# SCH_PCB-Hacker-Card_2024-02-11.net
KiCad netlist of a schematic drawn in EasyEDA
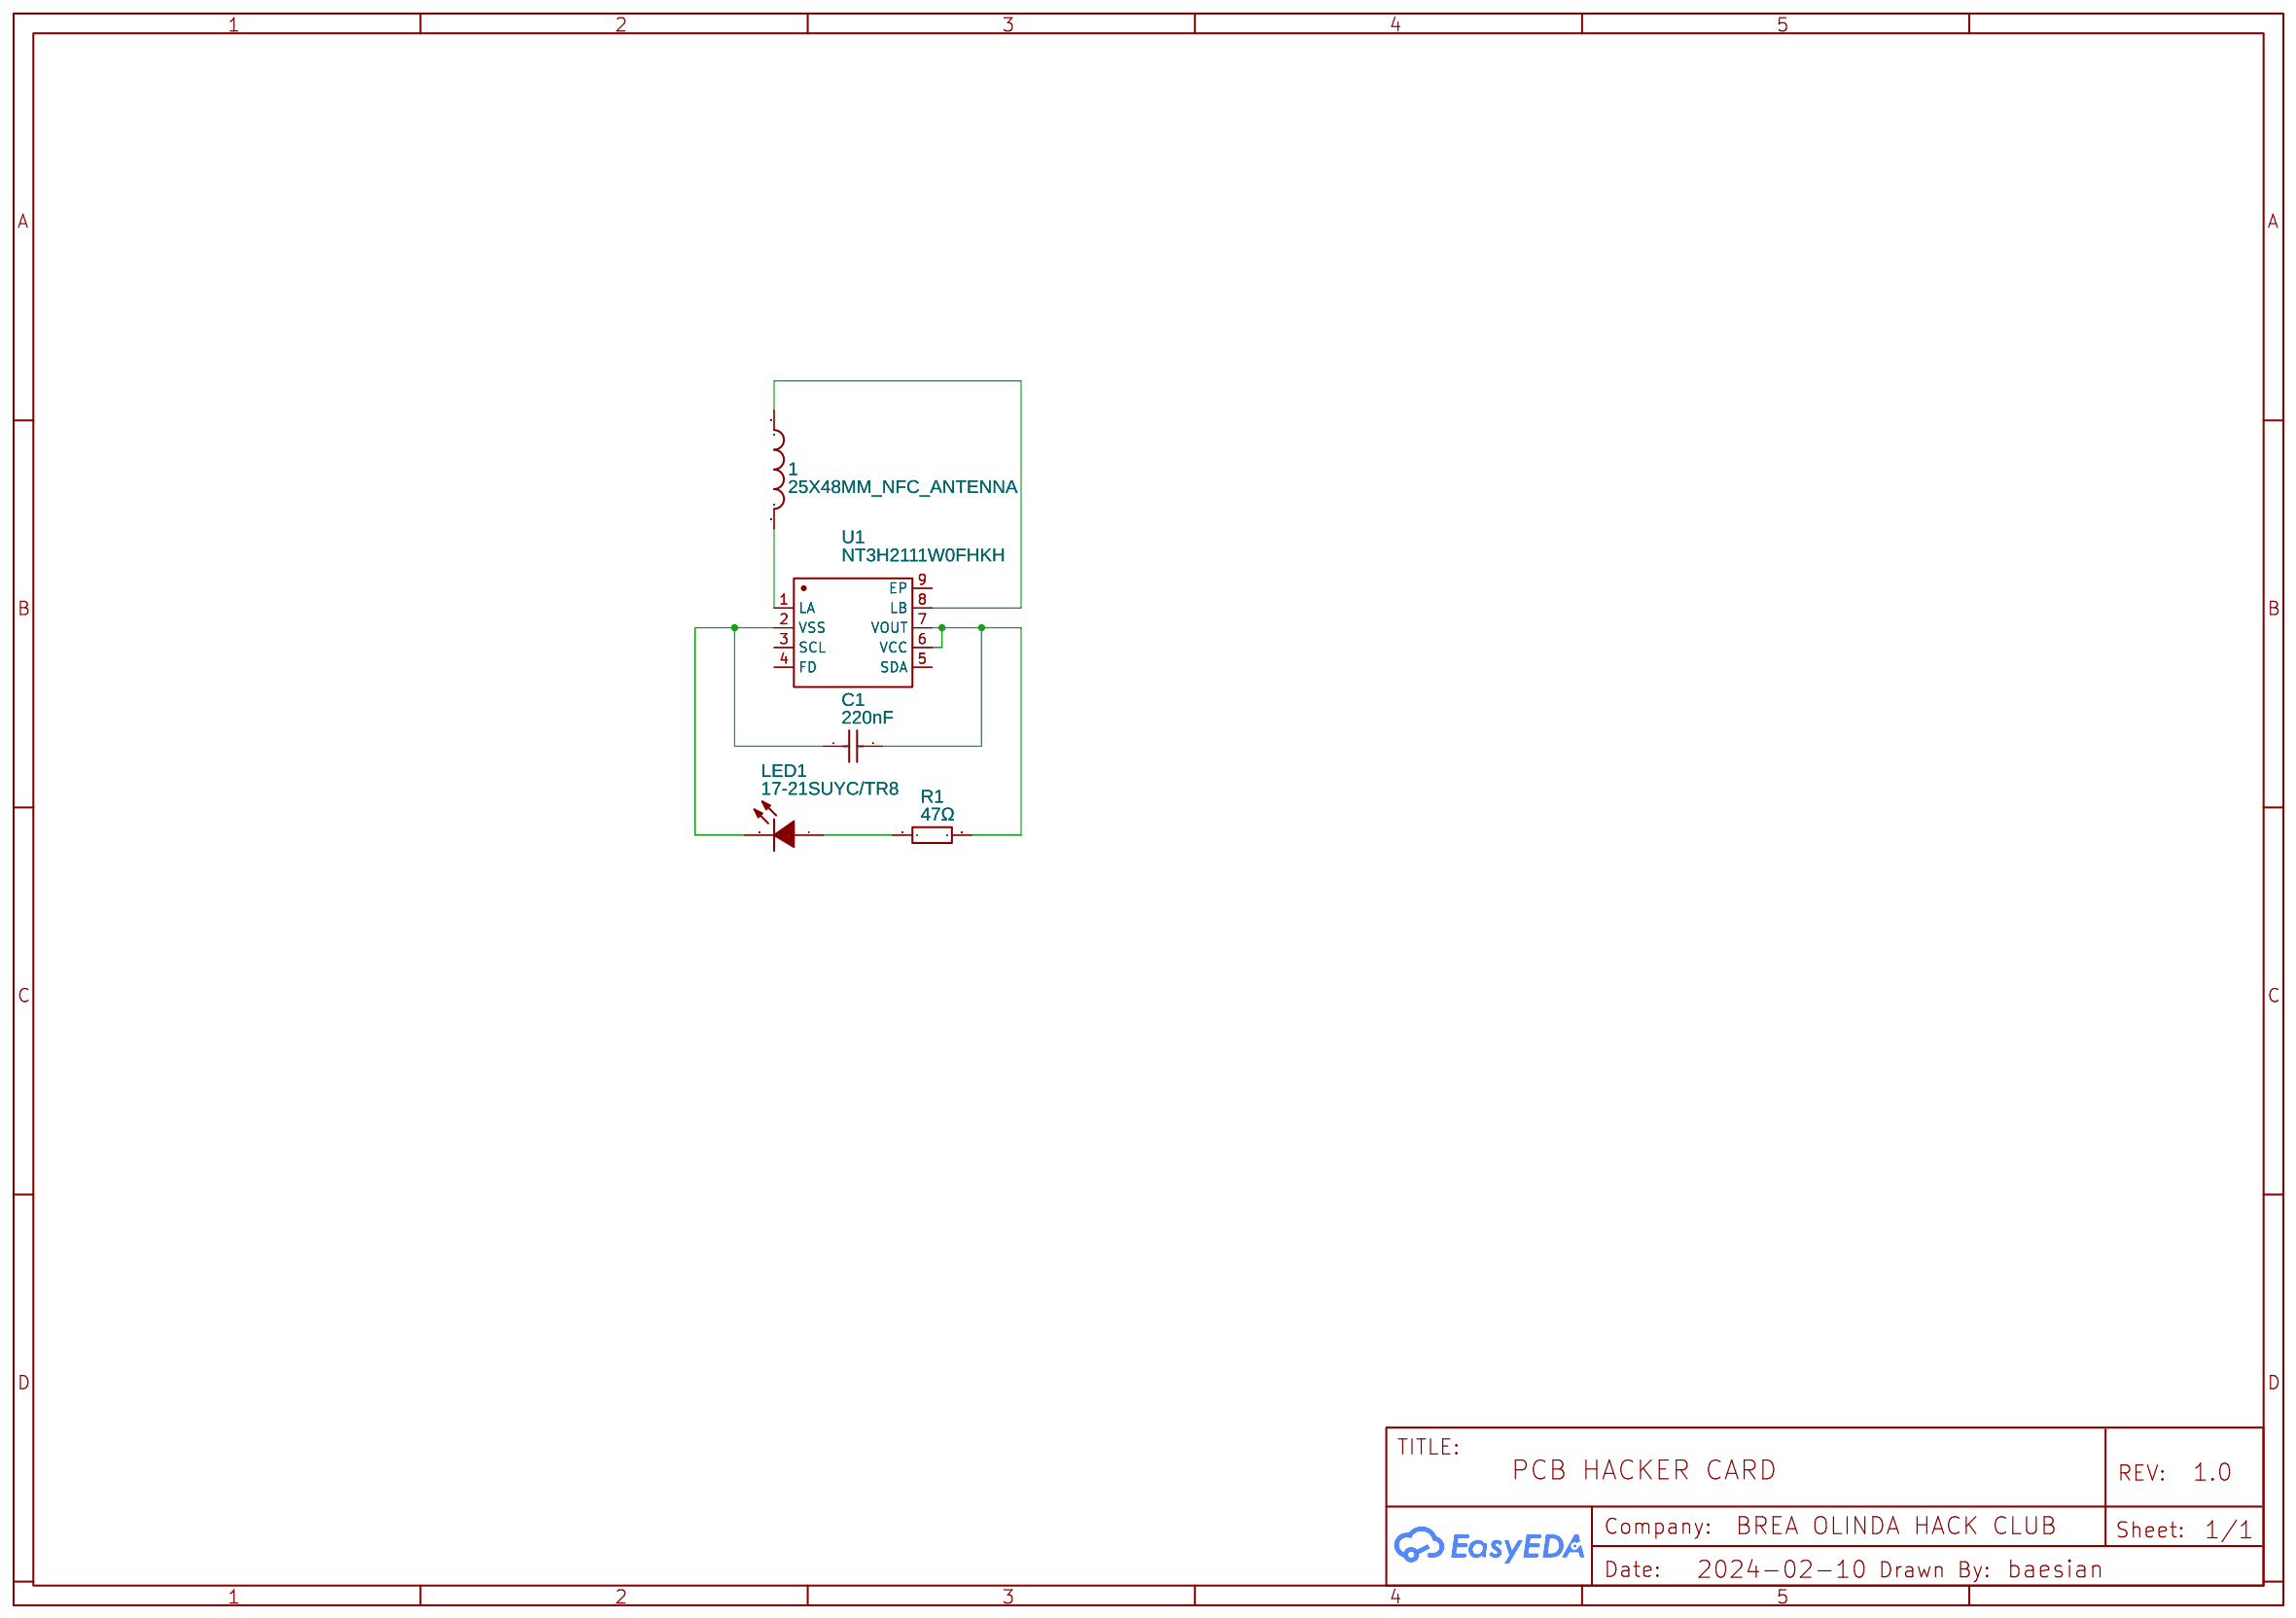
[diagram p0: schematic sheet]

(export (version "E")
  (design (tool "Eeschema 10.0.6"))
  (components
    (comp (ref "1") (value "25X48MM_NFC_ANTENNA") (libsource (lib "") (part "25X48MM_NFC_ANTENNA")))
    (comp (ref "C1")
      (value "220nF")
      (fields
        (field (name "Manufacturer Part") "CL10B224KA8NNNC")
        (field (name "Manufacturer") "SAMSUNG(三星)")
      )
      (libsource (lib "") (part "CL10B224KA8NNNC"))
    )
    (comp (ref "LED1")
      (value "17-21SUYC/TR8")
      (fields (field (name "Manufacturer Part") "KT-0805黄灯") (field (name "Manufacturer") "KENTO"))
      (libsource (lib "") (part "17-21SUYC/TR8"))
    )
    (comp (ref "R1")
      (value "47Ω")
      (fields
        (field (name "Manufacturer Part") "0603WAF470JT5E")
        (field (name "Manufacturer") "UNI-ROYAL(厚声)")
      )
      (libsource (lib "") (part "0603WAF470JT5E"))
    )
    (comp (ref "U1")
      (value "NT3H2111W0FHKH")
      (fields (field (name "Manufacturer") "NXP(恩智浦)"))
      (libsource (lib "") (part "NT3H2111W0FHKH"))
    )
  )
  (nets
    (net (code "1") (name "Net-(LED1-+)") (class "Default")
      (node (ref "LED1") (pin "1") (pinfunction "+_1") (pintype "unspecified"))
      (node (ref "R1") (pin "1") (pinfunction "1_1") (pintype "input"))
    )
    (net (code "2") (name "Net-(LED1--)") (class "Default")
      (node (ref "C1") (pin "1") (pinfunction "1_1") (pintype "input"))
      (node (ref "LED1") (pin "2") (pinfunction "-_2") (pintype "unspecified"))
      (node (ref "U1") (pin "2") (pinfunction "VSS_2") (pintype "unspecified"))
    )
    (net (code "3") (name "Net-(U1-LA)") (class "Default")
      (node (ref "1") (pin "P$2") (pinfunction "P$2_P$2") (pintype "bidirectional"))
      (node (ref "U1") (pin "1") (pinfunction "LA_1") (pintype "unspecified"))
    )
    (net (code "4") (name "Net-(U1-LB)") (class "Default")
      (node (ref "1") (pin "P$1") (pinfunction "P$1_P$1") (pintype "bidirectional"))
      (node (ref "U1") (pin "8") (pinfunction "LB_8") (pintype "unspecified"))
    )
    (net (code "5") (name "Net-(U1-VCC)") (class "Default")
      (node (ref "C1") (pin "2") (pinfunction "2_2") (pintype "input"))
      (node (ref "R1") (pin "2") (pinfunction "2_2") (pintype "input"))
      (node (ref "U1") (pin "6") (pinfunction "VCC_6") (pintype "unspecified"))
      (node (ref "U1") (pin "7") (pinfunction "VOUT_7") (pintype "unspecified"))
    )
    (net (code "6") (name "unconnected-(U1-EP-Pad9)") (class "Default")
      (node (ref "U1") (pin "9") (pinfunction "EP_9") (pintype "unspecified"))
    )
    (net (code "7") (name "unconnected-(U1-FD-Pad4)") (class "Default")
      (node (ref "U1") (pin "4") (pinfunction "FD_4") (pintype "unspecified"))
    )
    (net (code "8") (name "unconnected-(U1-SCL-Pad3)") (class "Default")
      (node (ref "U1") (pin "3") (pinfunction "SCL_3") (pintype "unspecified"))
    )
    (net (code "9") (name "unconnected-(U1-SDA-Pad5)") (class "Default")
      (node (ref "U1") (pin "5") (pinfunction "SDA_5") (pintype "unspecified"))
    )
  )
)
